# afron_atmega328_PTH.net
KiCad netlist of a schematic drawn in EAGLE
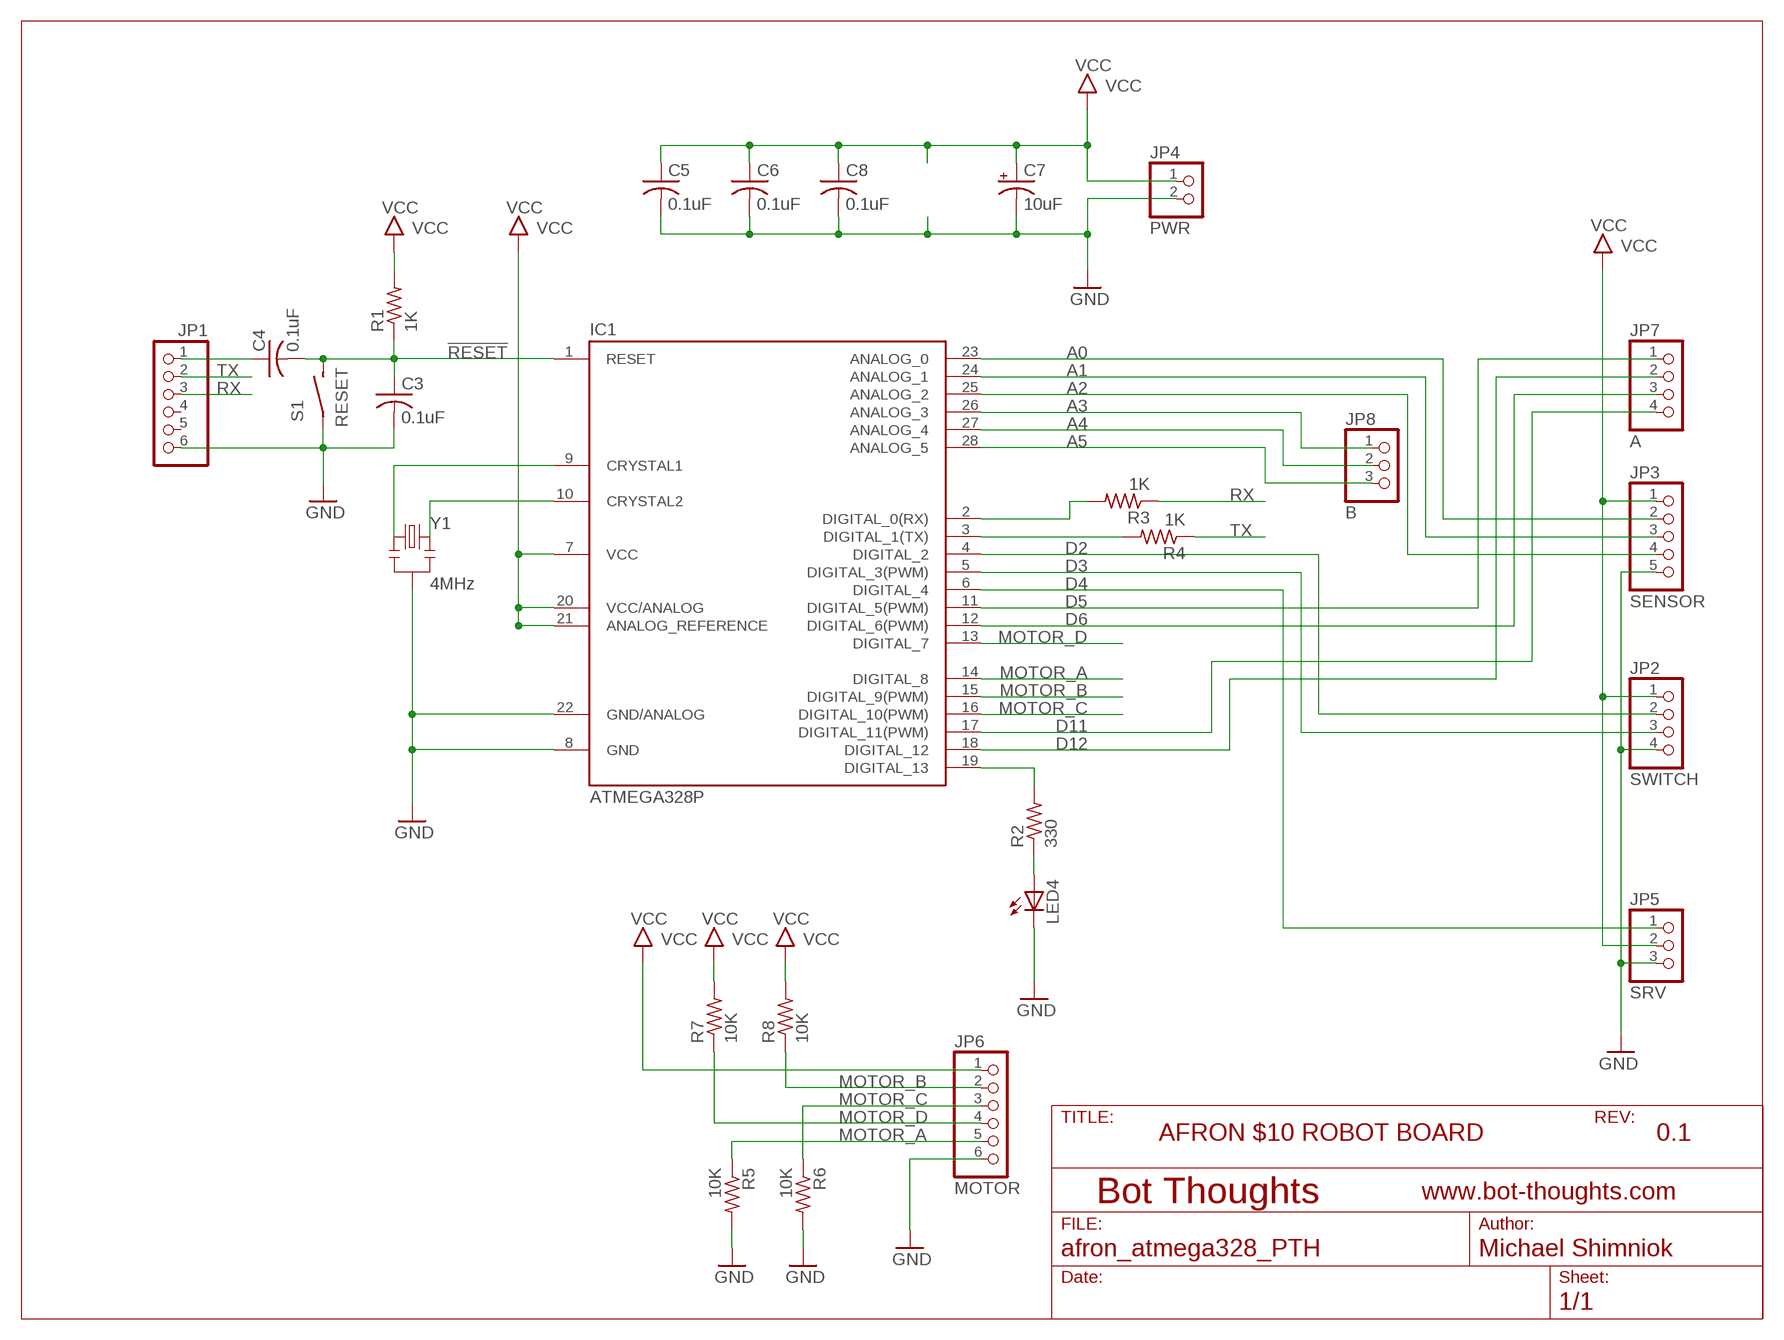
[diagram p0: schematic, sheet 1]

(export (version "E")
  (design (tool "Eeschema 10.0.6"))
  (components
    (comp (ref "C3")
      (value "0.1uF")
      (footprint "eagle-import:C050-024X044")
      (libsource (lib "eagle-import") (part "C-US050-024X044"))
    )
    (comp (ref "C4")
      (value "0.1uF")
      (footprint "eagle-import:C050-024X044")
      (libsource (lib "eagle-import") (part "C-US050-024X044"))
    )
    (comp (ref "C5")
      (value "0.1uF")
      (footprint "eagle-import:C0603")
      (libsource (lib "eagle-import") (part "C-USC0603"))
    )
    (comp (ref "C6")
      (value "0.1uF")
      (footprint "eagle-import:C050-024X044")
      (libsource (lib "eagle-import") (part "C-US050-024X044"))
    )
    (comp (ref "C7")
      (value "10uF")
      (footprint "eagle-import:E2,5-6")
      (libsource (lib "eagle-import") (part "CPOL-USE2.5-6"))
    )
    (comp (ref "C8")
      (value "0.1uF")
      (footprint "eagle-import:C050-024X044")
      (libsource (lib "eagle-import") (part "C-US050-024X044"))
    )
    (comp (ref "IC1")
      (value "ATMEGA328P")
      (footprint "eagle-import:DIL28-3")
      (libsource (lib "eagle-import") (part "ATMEGA168-PU"))
    )
    (comp (ref "JP1")
      (value "PINHD-1X06_2.54-S")
      (footprint "eagle-import:1X06-S")
      (libsource (lib "eagle-import") (part "PINHD-1X06_2.54-S"))
    )
    (comp (ref "JP2")
      (value "SWITCH")
      (footprint "eagle-import:1X04-S")
      (libsource (lib "eagle-import") (part "PINHD-1X04_2.54-S"))
    )
    (comp (ref "JP3")
      (value "SENSOR")
      (footprint "eagle-import:1X05-S")
      (libsource (lib "eagle-import") (part "PINHD-1X05_2.54-S"))
    )
    (comp (ref "JP4")
      (value "PWR")
      (footprint "eagle-import:1X02-S")
      (libsource (lib "eagle-import") (part "PINHD-1X02_2.54-S"))
    )
    (comp (ref "JP5")
      (value "SRV")
      (footprint "eagle-import:1X03-S")
      (libsource (lib "eagle-import") (part "PINHD-1X03_2.54-S"))
    )
    (comp (ref "JP6")
      (value "MOTOR")
      (footprint "eagle-import:1X06-S")
      (libsource (lib "eagle-import") (part "PINHD-1X06_2.54-S"))
    )
    (comp (ref "JP7")
      (value "A")
      (footprint "eagle-import:1X04-S")
      (libsource (lib "eagle-import") (part "PINHD-1X04_2.54-S"))
    )
    (comp (ref "JP8")
      (value "B")
      (footprint "eagle-import:1X03-S")
      (libsource (lib "eagle-import") (part "PINHD-1X03_2.54-S"))
    )
    (comp (ref "LED4")
      (value "LED3MM")
      (footprint "eagle-import:LED3MM")
      (libsource (lib "eagle-import") (part "LED3MM"))
    )
    (comp (ref "R1")
      (value "1K")
      (footprint "eagle-import:0204_5")
      (libsource (lib "eagle-import") (part "R-US_0204/5"))
    )
    (comp (ref "R2")
      (value "330")
      (footprint "eagle-import:0204_5")
      (libsource (lib "eagle-import") (part "R-US_0204/5"))
    )
    (comp (ref "R3")
      (value "1K")
      (footprint "eagle-import:0204_5")
      (libsource (lib "eagle-import") (part "R-US_0204/5"))
    )
    (comp (ref "R4")
      (value "1K")
      (footprint "eagle-import:0204_5")
      (libsource (lib "eagle-import") (part "R-US_0204/5"))
    )
    (comp (ref "R5")
      (value "10K")
      (footprint "eagle-import:R0603")
      (libsource (lib "eagle-import") (part "R-US_R0603"))
    )
    (comp (ref "R6")
      (value "10K")
      (footprint "eagle-import:R0603")
      (libsource (lib "eagle-import") (part "R-US_R0603"))
    )
    (comp (ref "R7")
      (value "10K")
      (footprint "eagle-import:R0603")
      (libsource (lib "eagle-import") (part "R-US_R0603"))
    )
    (comp (ref "R8")
      (value "10K")
      (footprint "eagle-import:R0603")
      (libsource (lib "eagle-import") (part "R-US_R0603"))
    )
    (comp (ref "S1")
      (value "RESET")
      (footprint "eagle-import:6MMTACTILE")
      (libsource (lib "eagle-import") (part "SPST_TACT2"))
    )
    (comp (ref "Y1")
      (value "4MHz")
      (footprint "eagle-import:RESONATOR-PTH")
      (libsource (lib "eagle-import") (part "RESONATORPTH"))
    )
  )
  (nets
    (net (code "1") (name "/A0") (class "Default")
      (node (ref "IC1") (pin "23") (pinfunction "ANALOG_0_23") (pintype "bidirectional"))
      (node (ref "JP3") (pin "2") (pinfunction "2_2") (pintype "passive"))
    )
    (net (code "2") (name "/A1") (class "Default")
      (node (ref "IC1") (pin "24") (pinfunction "ANALOG_1_24") (pintype "bidirectional"))
      (node (ref "JP3") (pin "3") (pinfunction "3_3") (pintype "passive"))
    )
    (net (code "3") (name "/A2") (class "Default")
      (node (ref "IC1") (pin "25") (pinfunction "ANALOG_2_25") (pintype "bidirectional"))
      (node (ref "JP3") (pin "4") (pinfunction "4_4") (pintype "passive"))
    )
    (net (code "4") (name "/A3") (class "Default")
      (node (ref "IC1") (pin "26") (pinfunction "ANALOG_3_26") (pintype "bidirectional"))
      (node (ref "JP8") (pin "1") (pinfunction "1_1") (pintype "passive"))
    )
    (net (code "5") (name "/A4") (class "Default")
      (node (ref "IC1") (pin "27") (pinfunction "ANALOG_4_27") (pintype "bidirectional"))
      (node (ref "JP8") (pin "2") (pinfunction "2_2") (pintype "passive"))
    )
    (net (code "6") (name "/A5") (class "Default")
      (node (ref "IC1") (pin "28") (pinfunction "ANALOG_5_28") (pintype "bidirectional"))
      (node (ref "JP8") (pin "3") (pinfunction "3_3") (pintype "passive"))
    )
    (net (code "7") (name "/D2") (class "Default")
      (node (ref "IC1") (pin "4") (pinfunction "DIGITAL_2_4") (pintype "bidirectional"))
      (node (ref "JP2") (pin "2") (pinfunction "2_2") (pintype "passive"))
    )
    (net (code "8") (name "/D3") (class "Default")
      (node (ref "IC1") (pin "5") (pinfunction "DIGITAL_3(PWM)_5") (pintype "bidirectional"))
      (node (ref "JP2") (pin "3") (pinfunction "3_3") (pintype "passive"))
    )
    (net (code "9") (name "/D4") (class "Default")
      (node (ref "IC1") (pin "6") (pinfunction "DIGITAL_4_6") (pintype "bidirectional"))
      (node (ref "JP5") (pin "1") (pinfunction "1_1") (pintype "passive"))
    )
    (net (code "10") (name "/D5") (class "Default")
      (node (ref "IC1") (pin "11") (pinfunction "DIGITAL_5(PWM)_11") (pintype "bidirectional"))
      (node (ref "JP7") (pin "1") (pinfunction "1_1") (pintype "passive"))
    )
    (net (code "11") (name "/D6") (class "Default")
      (node (ref "IC1") (pin "12") (pinfunction "DIGITAL_6(PWM)_12") (pintype "bidirectional"))
      (node (ref "JP7") (pin "3") (pinfunction "3_3") (pintype "passive"))
    )
    (net (code "12") (name "/D11") (class "Default")
      (node (ref "IC1") (pin "17") (pinfunction "DIGITAL_11(PWM)_17") (pintype "bidirectional"))
      (node (ref "JP7") (pin "4") (pinfunction "4_4") (pintype "passive"))
    )
    (net (code "13") (name "/D12") (class "Default")
      (node (ref "IC1") (pin "18") (pinfunction "DIGITAL_12_18") (pintype "bidirectional"))
      (node (ref "JP7") (pin "2") (pinfunction "2_2") (pintype "passive"))
    )
    (net (code "14") (name "/MOTOR_A") (class "Default")
      (node (ref "IC1") (pin "14") (pinfunction "DIGITAL_8_14") (pintype "bidirectional"))
      (node (ref "JP6") (pin "5") (pinfunction "5_5") (pintype "passive"))
      (node (ref "R5") (pin "1") (pinfunction "1_1") (pintype "passive"))
    )
    (net (code "15") (name "/MOTOR_B") (class "Default")
      (node (ref "IC1") (pin "15") (pinfunction "DIGITAL_9(PWM)_15") (pintype "bidirectional"))
      (node (ref "JP6") (pin "2") (pinfunction "2_2") (pintype "passive"))
      (node (ref "R8") (pin "1") (pinfunction "1_1") (pintype "passive"))
    )
    (net (code "16") (name "/MOTOR_C") (class "Default")
      (node (ref "IC1") (pin "16") (pinfunction "DIGITAL_10(PWM)_16") (pintype "bidirectional"))
      (node (ref "JP6") (pin "3") (pinfunction "3_3") (pintype "passive"))
      (node (ref "R6") (pin "1") (pinfunction "1_1") (pintype "passive"))
    )
    (net (code "17") (name "/MOTOR_D") (class "Default")
      (node (ref "IC1") (pin "13") (pinfunction "DIGITAL_7_13") (pintype "bidirectional"))
      (node (ref "JP6") (pin "4") (pinfunction "4_4") (pintype "passive"))
      (node (ref "R7") (pin "1") (pinfunction "1_1") (pintype "passive"))
    )
    (net (code "18") (name "/RX") (class "Default")
      (node (ref "JP1") (pin "3") (pinfunction "3_3") (pintype "passive"))
      (node (ref "R3") (pin "1") (pinfunction "1_1") (pintype "passive"))
    )
    (net (code "19") (name "/TX") (class "Default")
      (node (ref "JP1") (pin "2") (pinfunction "2_2") (pintype "passive"))
      (node (ref "R4") (pin "1") (pinfunction "1_1") (pintype "passive"))
    )
    (net (code "20") (name "/~{RESET}") (class "Default")
      (node (ref "C3") (pin "1") (pinfunction "1_1") (pintype "passive"))
      (node (ref "C4") (pin "2") (pinfunction "2_2") (pintype "passive"))
      (node (ref "IC1") (pin "1") (pinfunction "RESET_1") (pintype "bidirectional"))
      (node (ref "R1") (pin "1") (pinfunction "1_1") (pintype "passive"))
      (node (ref "S1") (pin "P$2") (pinfunction "S_P$2") (pintype "passive"))
    )
    (net (code "21") (name "GND") (class "Default")
      (node (ref "C3") (pin "2") (pinfunction "2_2") (pintype "passive"))
      (node (ref "C5") (pin "2") (pinfunction "2_2") (pintype "passive"))
      (node (ref "C6") (pin "2") (pinfunction "2_2") (pintype "passive"))
      (node (ref "C7") (pin "-") (pinfunction "-_-") (pintype "passive"))
      (node (ref "C8") (pin "2") (pinfunction "2_2") (pintype "passive"))
      (node (ref "IC1") (pin "22") (pinfunction "GND/ANALOG_22") (pintype "power_in"))
      (node (ref "IC1") (pin "8") (pinfunction "GND_8") (pintype "power_in"))
      (node (ref "JP1") (pin "6") (pinfunction "6_6") (pintype "passive"))
      (node (ref "JP2") (pin "4") (pinfunction "4_4") (pintype "passive"))
      (node (ref "JP3") (pin "5") (pinfunction "5_5") (pintype "passive"))
      (node (ref "JP4") (pin "2") (pinfunction "2_2") (pintype "passive"))
      (node (ref "JP5") (pin "3") (pinfunction "3_3") (pintype "passive"))
      (node (ref "JP6") (pin "6") (pinfunction "6_6") (pintype "passive"))
      (node (ref "LED4") (pin "K") (pinfunction "C_K") (pintype "passive"))
      (node (ref "R5") (pin "2") (pinfunction "2_2") (pintype "passive"))
      (node (ref "R6") (pin "2") (pinfunction "2_2") (pintype "passive"))
      (node (ref "S1") (pin "P$1") (pinfunction "P_P$1") (pintype "passive"))
      (node (ref "Y1") (pin "2") (pinfunction "2_2") (pintype "passive"))
    )
    (net (code "22") (name "Net-(C4-Pad1)") (class "Default")
      (node (ref "C4") (pin "1") (pinfunction "1_1") (pintype "passive"))
      (node (ref "JP1") (pin "1") (pinfunction "1_1") (pintype "passive"))
    )
    (net (code "23") (name "Net-(IC1-CRYSTAL1)") (class "Default")
      (node (ref "IC1") (pin "9") (pinfunction "CRYSTAL1_9") (pintype "bidirectional"))
      (node (ref "Y1") (pin "1") (pinfunction "1_1") (pintype "passive"))
    )
    (net (code "24") (name "Net-(IC1-CRYSTAL2)") (class "Default")
      (node (ref "IC1") (pin "10") (pinfunction "CRYSTAL2_10") (pintype "bidirectional"))
      (node (ref "Y1") (pin "3") (pinfunction "3_3") (pintype "passive"))
    )
    (net (code "25") (name "Net-(IC1-DIGITAL_0(RX))") (class "Default")
      (node (ref "IC1") (pin "2") (pinfunction "DIGITAL_0(RX)_2") (pintype "bidirectional"))
      (node (ref "R3") (pin "2") (pinfunction "2_2") (pintype "passive"))
    )
    (net (code "26") (name "Net-(IC1-DIGITAL_1(TX))") (class "Default")
      (node (ref "IC1") (pin "3") (pinfunction "DIGITAL_1(TX)_3") (pintype "bidirectional"))
      (node (ref "R4") (pin "2") (pinfunction "2_2") (pintype "passive"))
    )
    (net (code "27") (name "Net-(IC1-DIGITAL_13)") (class "Default")
      (node (ref "IC1") (pin "19") (pinfunction "DIGITAL_13_19") (pintype "bidirectional"))
      (node (ref "R2") (pin "2") (pinfunction "2_2") (pintype "passive"))
    )
    (net (code "28") (name "Net-(LED4-PadA)") (class "Default")
      (node (ref "LED4") (pin "A") (pinfunction "A_A") (pintype "passive"))
      (node (ref "R2") (pin "1") (pinfunction "1_1") (pintype "passive"))
    )
    (net (code "29") (name "VCC") (class "Default")
      (node (ref "C5") (pin "1") (pinfunction "1_1") (pintype "passive"))
      (node (ref "C6") (pin "1") (pinfunction "1_1") (pintype "passive"))
      (node (ref "C7") (pin "+") (pinfunction "+_+") (pintype "passive"))
      (node (ref "C8") (pin "1") (pinfunction "1_1") (pintype "passive"))
      (node (ref "IC1") (pin "20") (pinfunction "VCC/ANALOG_20") (pintype "passive"))
      (node (ref "IC1") (pin "21") (pinfunction "ANALOG_REFERENCE_21") (pintype "passive"))
      (node (ref "IC1") (pin "7") (pinfunction "VCC_7") (pintype "power_in"))
      (node (ref "JP2") (pin "1") (pinfunction "1_1") (pintype "passive"))
      (node (ref "JP3") (pin "1") (pinfunction "1_1") (pintype "passive"))
      (node (ref "JP4") (pin "1") (pinfunction "1_1") (pintype "passive"))
      (node (ref "JP5") (pin "2") (pinfunction "2_2") (pintype "passive"))
      (node (ref "JP6") (pin "1") (pinfunction "1_1") (pintype "passive"))
      (node (ref "R1") (pin "2") (pinfunction "2_2") (pintype "passive"))
      (node (ref "R7") (pin "2") (pinfunction "2_2") (pintype "passive"))
      (node (ref "R8") (pin "2") (pinfunction "2_2") (pintype "passive"))
    )
    (net (code "30") (name "unconnected-(JP1-Pad4)") (class "Default")
      (node (ref "JP1") (pin "4") (pinfunction "4_4") (pintype "passive"))
    )
    (net (code "31") (name "unconnected-(JP1-Pad5)") (class "Default")
      (node (ref "JP1") (pin "5") (pinfunction "5_5") (pintype "passive"))
    )
  )
)
